# Hahnentrittstulpe.net
KiCad netlist of a schematic drawn in EAGLE
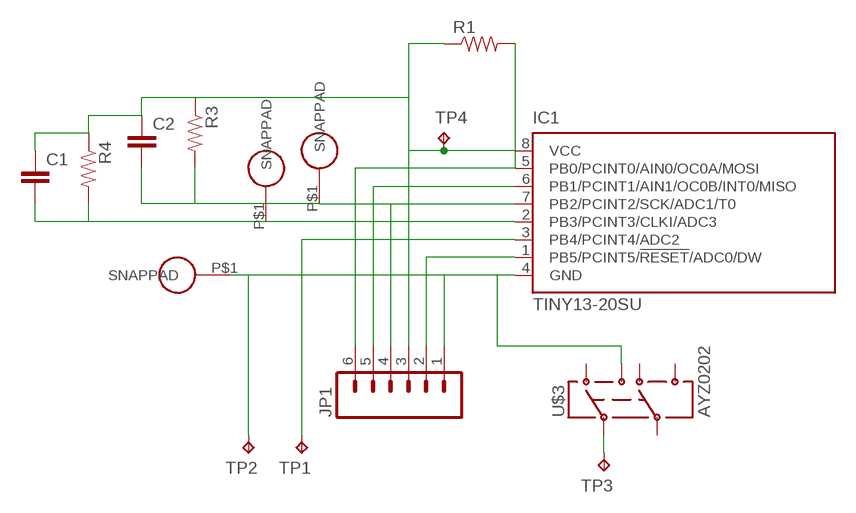
[diagram p0: schematic, sheet 1]

(export (version "E")
  (design (tool "Eeschema 10.0.6"))
  (components
    (comp (ref "C1")
      (value "CAP0603-CAP")
      (footprint "eagle-import:0603-CAP")
      (libsource (lib "eagle-import") (part "CAP0603-CAP"))
    )
    (comp (ref "C2")
      (value "CAP0603-CAP")
      (footprint "eagle-import:0603-CAP")
      (libsource (lib "eagle-import") (part "CAP0603-CAP"))
    )
    (comp (ref "IC1")
      (value "TINY13-20SU")
      (footprint "eagle-import:8S2")
      (fields (field (name "MPN") "ATTINY13-20SU"))
      (libsource (lib "eagle-import") (part "TINY13SU-20"))
    )
    (comp (ref "JP1")
      (value "M06SMD")
      (footprint "eagle-import:1X06-SMD")
      (libsource (lib "eagle-import") (part "M06SMD"))
    )
    (comp (ref "R1")
      (value "RESISTOR1206")
      (footprint "eagle-import:1206")
      (libsource (lib "eagle-import") (part "SparkFun-Resistors_RESISTOR1206"))
    )
    (comp (ref "R3")
      (value "RESISTOR0402-RES")
      (footprint "eagle-import:0402-RES")
      (libsource (lib "eagle-import") (part "RESISTOR0402-RES"))
    )
    (comp (ref "R4")
      (value "RESISTOR0402-RES")
      (footprint "eagle-import:0402-RES")
      (libsource (lib "eagle-import") (part "RESISTOR0402-RES"))
    )
    (comp (ref "TP1")
      (value "TPTP18SQ")
      (footprint "eagle-import:TP18SQ")
      (libsource (lib "eagle-import") (part "TPTP18SQ"))
    )
    (comp (ref "TP2")
      (value "TPTP18SQ")
      (footprint "eagle-import:TP18SQ")
      (libsource (lib "eagle-import") (part "TPTP18SQ"))
    )
    (comp (ref "TP3")
      (value "TPTP18SQ")
      (footprint "eagle-import:TP18SQ")
      (libsource (lib "eagle-import") (part "TPTP18SQ"))
    )
    (comp (ref "TP4")
      (value "TPTP18SQ")
      (footprint "eagle-import:TP18SQ")
      (libsource (lib "eagle-import") (part "TPTP18SQ"))
    )
    (comp (ref "U$1")
      (value "SNAP-PAD_7MM_ROUND")
      (footprint "eagle-import:SNAP-PAD_7MM_RD")
      (libsource (lib "eagle-import") (part "SNAP-PAD_7MM_ROUND"))
    )
    (comp (ref "U$2")
      (value "SNAP-PAD_7MM_ROUND")
      (footprint "eagle-import:SNAP-PAD_7MM_RD")
      (libsource (lib "eagle-import") (part "SNAP-PAD_7MM_ROUND"))
    )
    (comp (ref "U$3")
      (value "AYZ0202")
      (footprint "eagle-import:AYZ0202")
      (libsource (lib "eagle-import") (part "AYZ0202"))
    )
    (comp (ref "U$4")
      (value "SNAP-PAD_7MM_ROUND")
      (footprint "eagle-import:SNAP-PAD_7MM_RD")
      (libsource (lib "eagle-import") (part "SNAP-PAD_7MM_ROUND"))
    )
  )
  (nets
    (net (code "1") (name "Net-(IC1-GND)") (class "Default")
      (node (ref "IC1") (pin "4") (pinfunction "GND_4") (pintype "power_in"))
      (node (ref "JP1") (pin "1") (pinfunction "1_1") (pintype "passive"))
      (node (ref "TP2") (pin "TP") (pinfunction "TP_TP") (pintype "input"))
      (node (ref "U$3") (pin "1") (pinfunction "3_1") (pintype "bidirectional"))
      (node (ref "U$4") (pin "P$1") (pinfunction "SNAPPAD_P$1") (pintype "bidirectional"))
    )
    (net (code "2") (name "Net-(IC1-PB0{slash}PCINT0{slash}AIN0{slash}OC0A{slash}MOSI)") (class "Default")
      (node (ref "IC1") (pin "5") (pinfunction "PB0/PCINT0/AIN0/OC0A/MOSI_5") (pintype "bidirectional"))
      (node (ref "JP1") (pin "6") (pinfunction "6_6") (pintype "passive"))
      (node (ref "R1") (pin "2") (pinfunction "2_2") (pintype "passive"))
    )
    (net (code "3") (name "Net-(IC1-PB1{slash}PCINT1{slash}AIN1{slash}OC0B{slash}INT0{slash}MISO)") (class "Default")
      (node (ref "IC1") (pin "6") (pinfunction "PB1/PCINT1/AIN1/OC0B/INT0/MISO_6") (pintype "bidirectional"))
      (node (ref "JP1") (pin "5") (pinfunction "5_5") (pintype "passive"))
    )
    (net (code "4") (name "Net-(IC1-PB2{slash}PCINT2{slash}SCK{slash}ADC1{slash}T0)") (class "Default")
      (node (ref "C2") (pin "2") (pinfunction "2_2") (pintype "passive"))
      (node (ref "IC1") (pin "7") (pinfunction "PB2/PCINT2/SCK/ADC1/T0_7") (pintype "bidirectional"))
      (node (ref "JP1") (pin "4") (pinfunction "4_4") (pintype "passive"))
      (node (ref "R3") (pin "2") (pinfunction "2_2") (pintype "passive"))
      (node (ref "U$2") (pin "P$1") (pinfunction "SNAPPAD_P$1") (pintype "bidirectional"))
    )
    (net (code "5") (name "Net-(IC1-PB3{slash}PCINT3{slash}CLKI{slash}ADC3)") (class "Default")
      (node (ref "C1") (pin "2") (pinfunction "2_2") (pintype "passive"))
      (node (ref "IC1") (pin "2") (pinfunction "PB3/PCINT3/CLKI/ADC3_2") (pintype "bidirectional"))
      (node (ref "R4") (pin "2") (pinfunction "2_2") (pintype "passive"))
      (node (ref "U$1") (pin "P$1") (pinfunction "SNAPPAD_P$1") (pintype "bidirectional"))
    )
    (net (code "6") (name "Net-(IC1-PB4{slash}PCINT4{slash}ADC2)") (class "Default")
      (node (ref "IC1") (pin "3") (pinfunction "PB4/PCINT4/ADC2_3") (pintype "bidirectional"))
      (node (ref "TP1") (pin "TP") (pinfunction "TP_TP") (pintype "input"))
    )
    (net (code "7") (name "Net-(IC1-PB5{slash}PCINT5{slash}~{RESET}{slash}ADC0{slash}DW)") (class "Default")
      (node (ref "IC1") (pin "1") (pinfunction "PB5/PCINT5/~{RESET}/ADC0/DW_1") (pintype "bidirectional"))
      (node (ref "JP1") (pin "2") (pinfunction "2_2") (pintype "passive"))
    )
    (net (code "8") (name "Net-(IC1-VCC)") (class "Default")
      (node (ref "C1") (pin "1") (pinfunction "1_1") (pintype "passive"))
      (node (ref "C2") (pin "1") (pinfunction "1_1") (pintype "passive"))
      (node (ref "IC1") (pin "8") (pinfunction "VCC_8") (pintype "power_in"))
      (node (ref "JP1") (pin "3") (pinfunction "3_3") (pintype "passive"))
      (node (ref "R1") (pin "1") (pinfunction "1_1") (pintype "passive"))
      (node (ref "R3") (pin "1") (pinfunction "1_1") (pintype "passive"))
      (node (ref "R4") (pin "1") (pinfunction "1_1") (pintype "passive"))
      (node (ref "TP4") (pin "TP") (pinfunction "TP_TP") (pintype "input"))
    )
    (net (code "9") (name "Net-(TP3-PadTP)") (class "Default")
      (node (ref "TP3") (pin "TP") (pinfunction "TP_TP") (pintype "input"))
      (node (ref "U$3") (pin "2") (pinfunction "2_2") (pintype "bidirectional"))
    )
    (net (code "10") (name "unconnected-(U$3-1-Pad3)") (class "Default")
      (node (ref "U$3") (pin "3") (pinfunction "1_3") (pintype "bidirectional"))
    )
    (net (code "11") (name "unconnected-(U$3-4-Pad6)") (class "Default")
      (node (ref "U$3") (pin "6") (pinfunction "4_6") (pintype "bidirectional"))
    )
    (net (code "12") (name "unconnected-(U$3-6-Pad4)") (class "Default")
      (node (ref "U$3") (pin "4") (pinfunction "6_4") (pintype "bidirectional"))
    )
    (net (code "13") (name "unconnected-(U$3-Pad5)") (class "Default")
      (node (ref "U$3") (pin "5") (pinfunction "5_5") (pintype "bidirectional"))
    )
  )
)
